# Memory.net
KiCad netlist of a schematic drawn in Altium Designer
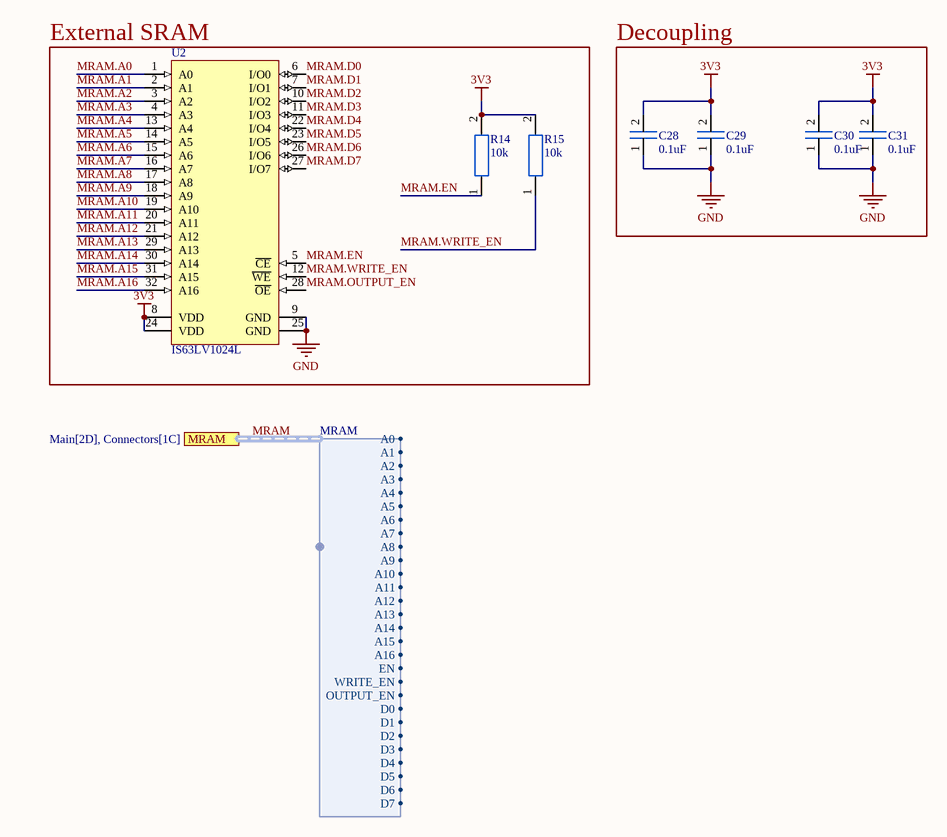
[diagram p0: Memory.SchDoc]

(export (version "E")
  (design (tool "Eeschema 10.0.6"))
  (components
    (comp (ref "C28")
      (value "0.1uF")
      (footprint "0402_footprint")
      (description "0402 capacitor")
      (libsource (lib "Schlib1") (part "Capacitor_0402"))
    )
    (comp (ref "C29")
      (value "0.1uF")
      (footprint "0402_footprint")
      (description "0402 capacitor")
      (libsource (lib "Schlib1") (part "Capacitor_0402"))
    )
    (comp (ref "C30")
      (value "0.1uF")
      (footprint "0402_footprint")
      (description "0402 capacitor")
      (libsource (lib "Schlib1") (part "Capacitor_0402"))
    )
    (comp (ref "C31")
      (value "0.1uF")
      (footprint "0402_footprint")
      (description "0402 capacitor")
      (libsource (lib "Schlib1") (part "Capacitor_0402"))
    )
    (comp (ref "R14")
      (value "10k")
      (footprint "0402_footprint")
      (libsource (lib "Schlib1") (part "Resistor_0402"))
    )
    (comp (ref "R15")
      (value "10k")
      (footprint "0402_footprint")
      (libsource (lib "Schlib1") (part "Resistor_0402"))
    )
    (comp (ref "U2")
      (value "IS63LV1024L")
      (footprint "ISSI-TSOP-2-32_N")
      (fields
        (field (name "MANUFACTURER") "Integrated Silicon Solution Inc (ISSI)")
        (field (name "PARTNUMBER") "IS61WV1288EEBLL-10TLI")
      )
      (libsource (lib "Altium Content Vault") (part "ISSI-IS61WV1288EEBLL-TSOP-2-32"))
    )
  )
  (nets
    (net (code "2") (name "/MRAM.A0") (class "Default")
      (node (ref "U2") (pin "1") (pinfunction "A0_1") (pintype "input"))
    )
    (net (code "3") (name "/MRAM.A1") (class "Default")
      (node (ref "U2") (pin "2") (pinfunction "A1_2") (pintype "input"))
    )
    (net (code "4") (name "/MRAM.A2") (class "Default")
      (node (ref "U2") (pin "3") (pinfunction "A2_3") (pintype "input"))
    )
    (net (code "5") (name "/MRAM.A3") (class "Default")
      (node (ref "U2") (pin "4") (pinfunction "A3_4") (pintype "input"))
    )
    (net (code "6") (name "/MRAM.A4") (class "Default")
      (node (ref "U2") (pin "13") (pinfunction "A4_13") (pintype "input"))
    )
    (net (code "7") (name "/MRAM.A5") (class "Default")
      (node (ref "U2") (pin "14") (pinfunction "A5_14") (pintype "input"))
    )
    (net (code "8") (name "/MRAM.A6") (class "Default")
      (node (ref "U2") (pin "15") (pinfunction "A6_15") (pintype "input"))
    )
    (net (code "9") (name "/MRAM.A7") (class "Default")
      (node (ref "U2") (pin "16") (pinfunction "A7_16") (pintype "input"))
    )
    (net (code "10") (name "/MRAM.A8") (class "Default")
      (node (ref "U2") (pin "17") (pinfunction "A8_17") (pintype "input"))
    )
    (net (code "11") (name "/MRAM.A9") (class "Default")
      (node (ref "U2") (pin "18") (pinfunction "A9_18") (pintype "input"))
    )
    (net (code "12") (name "/MRAM.A10") (class "Default")
      (node (ref "U2") (pin "19") (pinfunction "A10_19") (pintype "input"))
    )
    (net (code "13") (name "/MRAM.A11") (class "Default")
      (node (ref "U2") (pin "20") (pinfunction "A11_20") (pintype "input"))
    )
    (net (code "14") (name "/MRAM.A12") (class "Default")
      (node (ref "U2") (pin "21") (pinfunction "A12_21") (pintype "input"))
    )
    (net (code "15") (name "/MRAM.A13") (class "Default")
      (node (ref "U2") (pin "29") (pinfunction "A13_29") (pintype "input"))
    )
    (net (code "16") (name "/MRAM.A14") (class "Default")
      (node (ref "U2") (pin "30") (pinfunction "A14_30") (pintype "input"))
    )
    (net (code "17") (name "/MRAM.A15") (class "Default")
      (node (ref "U2") (pin "31") (pinfunction "A15_31") (pintype "input"))
    )
    (net (code "18") (name "/MRAM.A16") (class "Default")
      (node (ref "U2") (pin "32") (pinfunction "A16_32") (pintype "input"))
    )
    (net (code "19") (name "/MRAM.D0") (class "Default")
      (node (ref "U2") (pin "6") (pinfunction "I/O0_6") (pintype "bidirectional"))
    )
    (net (code "20") (name "/MRAM.D1") (class "Default")
      (node (ref "U2") (pin "7") (pinfunction "I/O1_7") (pintype "bidirectional"))
    )
    (net (code "21") (name "/MRAM.D2") (class "Default")
      (node (ref "U2") (pin "10") (pinfunction "I/O2_10") (pintype "bidirectional"))
    )
    (net (code "22") (name "/MRAM.D3") (class "Default")
      (node (ref "U2") (pin "11") (pinfunction "I/O3_11") (pintype "bidirectional"))
    )
    (net (code "23") (name "/MRAM.D4") (class "Default")
      (node (ref "U2") (pin "22") (pinfunction "I/O4_22") (pintype "bidirectional"))
    )
    (net (code "24") (name "/MRAM.D5") (class "Default")
      (node (ref "U2") (pin "23") (pinfunction "I/O5_23") (pintype "bidirectional"))
    )
    (net (code "25") (name "/MRAM.D6") (class "Default")
      (node (ref "U2") (pin "26") (pinfunction "I/O6_26") (pintype "bidirectional"))
    )
    (net (code "26") (name "/MRAM.D7") (class "Default")
      (node (ref "U2") (pin "27") (pinfunction "I/O7_27") (pintype "bidirectional"))
    )
    (net (code "27") (name "/MRAM.EN") (class "Default")
      (node (ref "R14") (pin "1") (pinfunction "1_1") (pintype "passive"))
      (node (ref "U2") (pin "5") (pinfunction "~{CE}_5") (pintype "input"))
    )
    (net (code "28") (name "/MRAM.OUTPUT_EN") (class "Default")
      (node (ref "U2") (pin "28") (pinfunction "~{OE}_28") (pintype "input"))
    )
    (net (code "29") (name "/MRAM.WRITE_EN") (class "Default")
      (node (ref "R15") (pin "1") (pinfunction "1_1") (pintype "passive"))
      (node (ref "U2") (pin "12") (pinfunction "~{WE}_12") (pintype "input"))
    )
    (net (code "31") (name "3V3") (class "Default")
      (node (ref "C28") (pin "2") (pinfunction "2_2") (pintype "passive"))
      (node (ref "C29") (pin "2") (pinfunction "2_2") (pintype "passive"))
      (node (ref "C30") (pin "2") (pinfunction "2_2") (pintype "passive"))
      (node (ref "C31") (pin "2") (pinfunction "2_2") (pintype "passive"))
      (node (ref "R14") (pin "2") (pinfunction "2_2") (pintype "passive"))
      (node (ref "R15") (pin "2") (pinfunction "2_2") (pintype "passive"))
      (node (ref "U2") (pin "24") (pinfunction "VDD_24") (pintype "power_in"))
      (node (ref "U2") (pin "8") (pinfunction "VDD_8") (pintype "power_in"))
    )
    (net (code "32") (name "GND") (class "Default")
      (node (ref "C28") (pin "1") (pinfunction "1_1") (pintype "passive"))
      (node (ref "C29") (pin "1") (pinfunction "1_1") (pintype "passive"))
      (node (ref "C30") (pin "1") (pinfunction "1_1") (pintype "passive"))
      (node (ref "C31") (pin "1") (pinfunction "1_1") (pintype "passive"))
      (node (ref "U2") (pin "25") (pinfunction "GND_25") (pintype "power_in"))
      (node (ref "U2") (pin "9") (pinfunction "GND_9") (pintype "power_in"))
    )
  )
)
